# tick-mini-mk-3_0.net
KiCad netlist of a schematic drawn in EAGLE
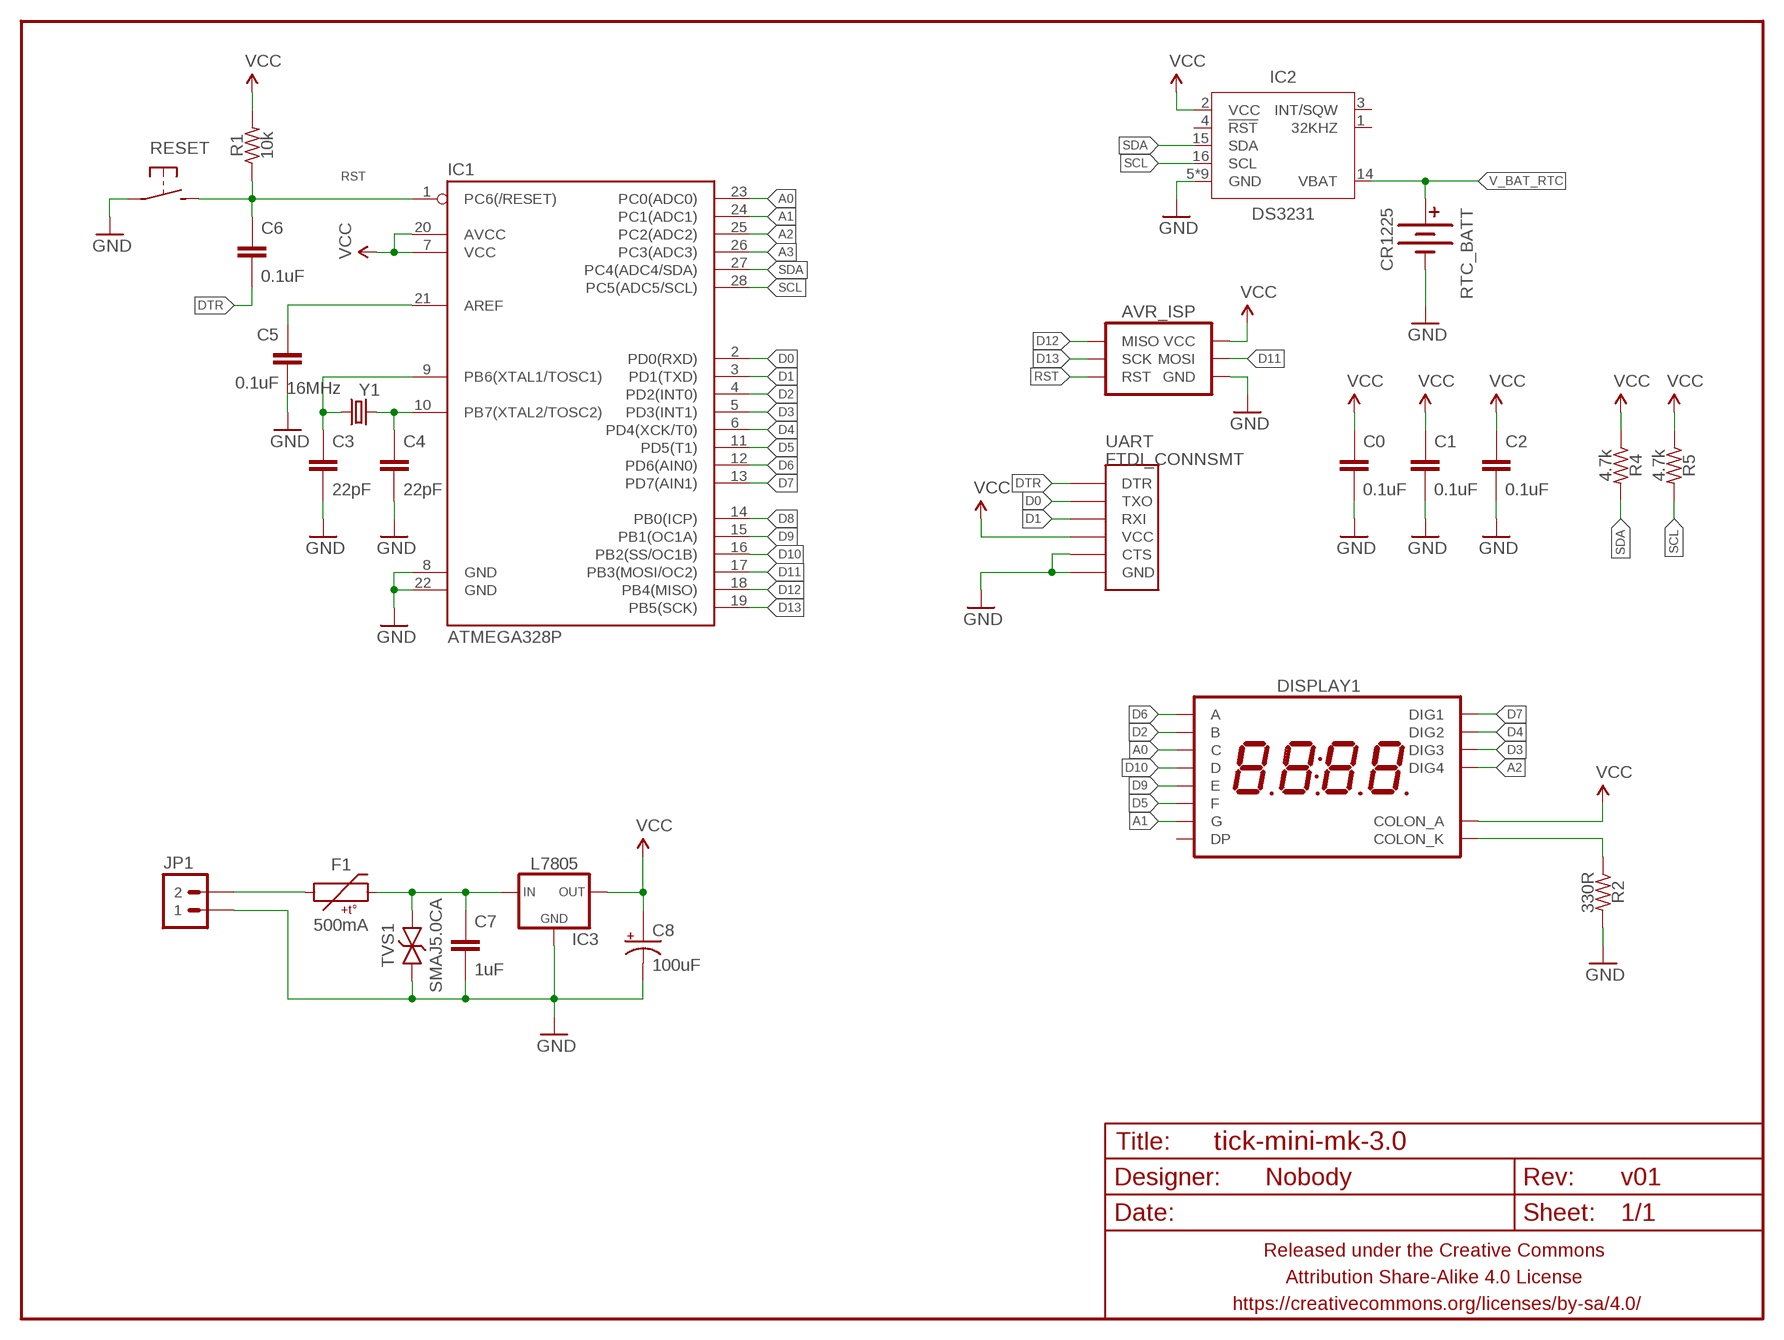
[diagram p0: schematic, sheet 1]

(export (version "E")
  (design (tool "Eeschema 10.0.6"))
  (components
    (comp (ref "AVR_ISP")
      (value "AVR_SPI_PRG_6PTH")
      (footprint "eagle-import:2X3")
      (libsource (lib "eagle-import") (part "AVR_SPI_PRG_6PTH"))
    )
    (comp (ref "C0")
      (value "0.1uF")
      (footprint "eagle-import:C0603")
      (libsource (lib "eagle-import") (part "CAPACITOR-CERAMICC0603"))
    )
    (comp (ref "C1")
      (value "0.1uF")
      (footprint "eagle-import:C0603")
      (libsource (lib "eagle-import") (part "CAPACITOR-CERAMICC0603"))
    )
    (comp (ref "C2")
      (value "0.1uF")
      (footprint "eagle-import:C0603")
      (libsource (lib "eagle-import") (part "CAPACITOR-CERAMICC0603"))
    )
    (comp (ref "C3")
      (value "22pF")
      (footprint "eagle-import:C0603")
      (libsource (lib "eagle-import") (part "CAPACITOR-CERAMICC0603"))
    )
    (comp (ref "C4")
      (value "22pF")
      (footprint "eagle-import:C0603")
      (libsource (lib "eagle-import") (part "CAPACITOR-CERAMICC0603"))
    )
    (comp (ref "C5")
      (value "0.1uF")
      (footprint "eagle-import:C0603")
      (libsource (lib "eagle-import") (part "CAPACITOR-CERAMICC0603"))
    )
    (comp (ref "C6")
      (value "0.1uF")
      (footprint "eagle-import:C0603")
      (libsource (lib "eagle-import") (part "CAPACITOR-CERAMICC0603"))
    )
    (comp (ref "C7")
      (value "1uF")
      (footprint "eagle-import:C0805")
      (libsource (lib "eagle-import") (part "CAPACITOR-CERAMICC0805"))
    )
    (comp (ref "C8")
      (value "100uF")
      (footprint "eagle-import:E2,5-5")
      (libsource (lib "eagle-import") (part "CAPACITOR-POLARIZEDE2.5-5"))
    )
    (comp (ref "DISPLAY1")
      (value "7SEG_4DIGIT_COLON14.2MM-CC-NS")
      (footprint "eagle-import:7SEG_4DIG_NS")
      (libsource (lib "eagle-import") (part "7SEG_4DIGIT_COLON14.2MM-CC-NS"))
    )
    (comp (ref "F1")
      (value "500mA")
      (footprint "eagle-import:PTC-1206")
      (libsource (lib "eagle-import") (part "PTCSMD"))
    )
    (comp (ref "FRAME1")
      (value "FRAME-LETTERNO_PACKAGE")
      (footprint "eagle-import:DUMMY")
      (fields (field (name "DESIGNER") "Nobody"))
      (libsource (lib "eagle-import") (part "FRAME-LETTERNO_PACKAGE"))
    )
    (comp (ref "IC1")
      (value "ATMEGA328P")
      (footprint "eagle-import:DIL28-3")
      (libsource (lib "eagle-import") (part "ATMEGA328P_PDIP"))
    )
    (comp (ref "IC2")
      (value "DS3231")
      (footprint "eagle-import:SO16W")
      (libsource (lib "eagle-import") (part "DS3231"))
    )
    (comp (ref "IC3")
      (value "L7805")
      (footprint "eagle-import:SO08")
      (libsource (lib "eagle-import") (part "V_REG_78XX"))
    )
    (comp (ref "JP1")
      (value "M02PTH-CENTERED-R+")
      (footprint "eagle-import:1X02-CENTER-R+")
      (libsource (lib "eagle-import") (part "M02PTH-CENTERED-R+"))
    )
    (comp (ref "R1")
      (value "10k")
      (footprint "eagle-import:R0603")
      (libsource (lib "eagle-import") (part "RESISTORR0603"))
    )
    (comp (ref "R2")
      (value "330R")
      (footprint "eagle-import:RESISTOR-AXIAL-PTH-7.62MM")
      (libsource (lib "eagle-import") (part "RESISTORPTH-AXIAL-7.62MM"))
    )
    (comp (ref "R4")
      (value "4.7k")
      (footprint "eagle-import:R0603")
      (libsource (lib "eagle-import") (part "RESISTORR0603"))
    )
    (comp (ref "R5")
      (value "4.7k")
      (footprint "eagle-import:R0603")
      (libsource (lib "eagle-import") (part "RESISTORR0603"))
    )
    (comp (ref "RESET")
      (value "SPST-NO-TACT3MM-PTH-SMALL-PADS")
      (footprint "eagle-import:DTS-3-SMALL-PADS")
      (libsource (lib "eagle-import") (part "SPST-NO-TACT3MM-PTH-SMALL-PADS"))
    )
    (comp (ref "RTC_BATT")
      (value "CR1225")
      (footprint "eagle-import:BATTCON_12MM")
      (libsource (lib "eagle-import") (part "BATTERY12MM"))
    )
    (comp (ref "TVS1")
      (value "SMAJ5.0CA")
      (footprint "eagle-import:SMA-DIODE-TVS-BIDIR")
      (libsource (lib "eagle-import") (part "TVSSMA"))
    )
    (comp (ref "UART")
      (value "FTDI_CONNSMT")
      (footprint "eagle-import:FTDI_CONN_SMT")
      (libsource (lib "eagle-import") (part "FTDI_CONNSMT"))
    )
    (comp (ref "Y1")
      (value "16MHz")
      (footprint "eagle-import:HC49U-V")
      (libsource (lib "eagle-import") (part "CRYSTALHC49UV"))
    )
  )
  (nets
    (net (code "1") (name "A0") (class "Default")
      (node (ref "DISPLAY1") (pin "P$4") (pinfunction "C_P$4") (pintype "passive"))
      (node (ref "IC1") (pin "23") (pinfunction "PC0(ADC0)_23") (pintype "bidirectional"))
    )
    (net (code "2") (name "A1") (class "Default")
      (node (ref "DISPLAY1") (pin "P$5") (pinfunction "G_P$5") (pintype "passive"))
      (node (ref "IC1") (pin "24") (pinfunction "PC1(ADC1)_24") (pintype "bidirectional"))
    )
    (net (code "3") (name "A2") (class "Default")
      (node (ref "DISPLAY1") (pin "P$6") (pinfunction "DIG4_P$6") (pintype "passive"))
      (node (ref "IC1") (pin "25") (pinfunction "PC2(ADC2)_25") (pintype "bidirectional"))
    )
    (net (code "4") (name "A3") (class "Default")
      (node (ref "IC1") (pin "26") (pinfunction "PC3(ADC3)_26") (pintype "bidirectional"))
    )
    (net (code "5") (name "D0") (class "Default")
      (node (ref "IC1") (pin "2") (pinfunction "PD0(RXD)_2") (pintype "bidirectional"))
      (node (ref "UART") (pin "TXO") (pinfunction "TXO_TXO") (pintype "bidirectional"))
    )
    (net (code "6") (name "D1") (class "Default")
      (node (ref "IC1") (pin "3") (pinfunction "PD1(TXD)_3") (pintype "bidirectional"))
      (node (ref "UART") (pin "RXI") (pinfunction "RXI_RXI") (pintype "bidirectional"))
    )
    (net (code "7") (name "D2") (class "Default")
      (node (ref "DISPLAY1") (pin "P$9") (pinfunction "B_P$9") (pintype "passive"))
      (node (ref "IC1") (pin "4") (pinfunction "PD2(INT0)_4") (pintype "bidirectional"))
    )
    (net (code "8") (name "D3") (class "Default")
      (node (ref "DISPLAY1") (pin "P$10") (pinfunction "DIG3_P$10") (pintype "passive"))
      (node (ref "IC1") (pin "5") (pinfunction "PD3(INT1)_5") (pintype "bidirectional"))
    )
    (net (code "9") (name "D4") (class "Default")
      (node (ref "DISPLAY1") (pin "P$11") (pinfunction "DIG2_P$11") (pintype "passive"))
      (node (ref "IC1") (pin "6") (pinfunction "PD4(XCK/T0)_6") (pintype "bidirectional"))
    )
    (net (code "10") (name "D5") (class "Default")
      (node (ref "DISPLAY1") (pin "P$12") (pinfunction "F_P$12") (pintype "passive"))
      (node (ref "IC1") (pin "11") (pinfunction "PD5(T1)_11") (pintype "bidirectional"))
    )
    (net (code "11") (name "D6") (class "Default")
      (node (ref "DISPLAY1") (pin "P$13") (pinfunction "A_P$13") (pintype "passive"))
      (node (ref "IC1") (pin "12") (pinfunction "PD6(AIN0)_12") (pintype "bidirectional"))
    )
    (net (code "12") (name "D7") (class "Default")
      (node (ref "DISPLAY1") (pin "P$14") (pinfunction "DIG1_P$14") (pintype "passive"))
      (node (ref "IC1") (pin "13") (pinfunction "PD7(AIN1)_13") (pintype "bidirectional"))
    )
    (net (code "13") (name "D8") (class "Default")
      (node (ref "IC1") (pin "14") (pinfunction "PB0(ICP)_14") (pintype "bidirectional"))
    )
    (net (code "14") (name "D9") (class "Default")
      (node (ref "DISPLAY1") (pin "P$1") (pinfunction "E_P$1") (pintype "passive"))
      (node (ref "IC1") (pin "15") (pinfunction "PB1(OC1A)_15") (pintype "bidirectional"))
    )
    (net (code "15") (name "D10") (class "Default")
      (node (ref "DISPLAY1") (pin "P$2") (pinfunction "D_P$2") (pintype "passive"))
      (node (ref "IC1") (pin "16") (pinfunction "PB2(SS/OC1B)_16") (pintype "bidirectional"))
    )
    (net (code "16") (name "D11") (class "Default")
      (node (ref "AVR_ISP") (pin "4") (pinfunction "MOSI_4") (pintype "passive"))
      (node (ref "IC1") (pin "17") (pinfunction "PB3(MOSI/OC2)_17") (pintype "bidirectional"))
    )
    (net (code "17") (name "D12") (class "Default")
      (node (ref "AVR_ISP") (pin "1") (pinfunction "MISO_1") (pintype "passive"))
      (node (ref "IC1") (pin "18") (pinfunction "PB4(MISO)_18") (pintype "bidirectional"))
    )
    (net (code "18") (name "D13") (class "Default")
      (node (ref "AVR_ISP") (pin "3") (pinfunction "SCK_3") (pintype "passive"))
      (node (ref "IC1") (pin "19") (pinfunction "PB5(SCK)_19") (pintype "bidirectional"))
    )
    (net (code "19") (name "DTR") (class "Default")
      (node (ref "C6") (pin "2") (pinfunction "2_2") (pintype "passive"))
      (node (ref "UART") (pin "DTR") (pinfunction "DTR_DTR") (pintype "bidirectional"))
    )
    (net (code "20") (name "GND") (class "Default")
      (node (ref "AVR_ISP") (pin "6") (pinfunction "GND_6") (pintype "passive"))
      (node (ref "C0") (pin "2") (pinfunction "2_2") (pintype "passive"))
      (node (ref "C1") (pin "2") (pinfunction "2_2") (pintype "passive"))
      (node (ref "C2") (pin "2") (pinfunction "2_2") (pintype "passive"))
      (node (ref "C3") (pin "2") (pinfunction "2_2") (pintype "passive"))
      (node (ref "C4") (pin "2") (pinfunction "2_2") (pintype "passive"))
      (node (ref "C5") (pin "2") (pinfunction "2_2") (pintype "passive"))
      (node (ref "C7") (pin "2") (pinfunction "2_2") (pintype "passive"))
      (node (ref "C8") (pin "-") (pinfunction "-_-") (pintype "passive"))
      (node (ref "IC1") (pin "22") (pinfunction "GND_22") (pintype "bidirectional"))
      (node (ref "IC1") (pin "8") (pinfunction "GND_8") (pintype "bidirectional"))
      (node (ref "IC2") (pin "10") (pinfunction "GND_10") (pintype "bidirectional"))
      (node (ref "IC2") (pin "11") (pinfunction "GND_11") (pintype "bidirectional"))
      (node (ref "IC2") (pin "12") (pinfunction "GND_12") (pintype "bidirectional"))
      (node (ref "IC2") (pin "13") (pinfunction "GND_13") (pintype "bidirectional"))
      (node (ref "IC2") (pin "5") (pinfunction "GND_5") (pintype "bidirectional"))
      (node (ref "IC2") (pin "6") (pinfunction "GND_6") (pintype "bidirectional"))
      (node (ref "IC2") (pin "7") (pinfunction "GND_7") (pintype "bidirectional"))
      (node (ref "IC2") (pin "8") (pinfunction "GND_8") (pintype "bidirectional"))
      (node (ref "IC2") (pin "9") (pinfunction "GND_9") (pintype "bidirectional"))
      (node (ref "IC3") (pin "2") (pinfunction "GND_2") (pintype "bidirectional"))
      (node (ref "IC3") (pin "3") (pinfunction "GND_3") (pintype "bidirectional"))
      (node (ref "IC3") (pin "4") (pinfunction "GND_4") (pintype "bidirectional"))
      (node (ref "IC3") (pin "5") (pinfunction "GND_5") (pintype "bidirectional"))
      (node (ref "IC3") (pin "6") (pinfunction "GND_6") (pintype "bidirectional"))
      (node (ref "IC3") (pin "7") (pinfunction "GND_7") (pintype "bidirectional"))
      (node (ref "JP1") (pin "1") (pinfunction "1_1") (pintype "passive"))
      (node (ref "R2") (pin "P$2") (pinfunction "2_P$2") (pintype "passive"))
      (node (ref "RESET") (pin "1") (pinfunction "1_1") (pintype "passive"))
      (node (ref "RTC_BATT") (pin "GND") (pinfunction "-_GND") (pintype "power_in"))
      (node (ref "TVS1") (pin "1") (pinfunction "1_1") (pintype "passive"))
      (node (ref "UART") (pin "CTS") (pinfunction "CTS_CTS") (pintype "bidirectional"))
      (node (ref "UART") (pin "GND") (pinfunction "GND_GND") (pintype "bidirectional"))
    )
    (net (code "21") (name "Net-(DISPLAY1-COLON_K)") (class "Default")
      (node (ref "DISPLAY1") (pin "P$7") (pinfunction "COLON_K_P$7") (pintype "passive"))
      (node (ref "R2") (pin "P$1") (pinfunction "1_P$1") (pintype "passive"))
    )
    (net (code "22") (name "Net-(F1-Pad1)") (class "Default")
      (node (ref "F1") (pin "1") (pinfunction "1_1") (pintype "passive"))
      (node (ref "JP1") (pin "2") (pinfunction "2_2") (pintype "passive"))
    )
    (net (code "23") (name "Net-(IC1-AREF)") (class "Default")
      (node (ref "C5") (pin "1") (pinfunction "1_1") (pintype "passive"))
      (node (ref "IC1") (pin "21") (pinfunction "AREF_21") (pintype "bidirectional"))
    )
    (net (code "24") (name "Net-(IC1-PB6(XTAL1{slash}TOSC1))") (class "Default")
      (node (ref "C3") (pin "1") (pinfunction "1_1") (pintype "passive"))
      (node (ref "IC1") (pin "9") (pinfunction "PB6(XTAL1/TOSC1)_9") (pintype "bidirectional"))
      (node (ref "Y1") (pin "2") (pinfunction "2_2") (pintype "passive"))
    )
    (net (code "25") (name "Net-(IC1-PB7(XTAL2{slash}TOSC2))") (class "Default")
      (node (ref "C4") (pin "1") (pinfunction "1_1") (pintype "passive"))
      (node (ref "IC1") (pin "10") (pinfunction "PB7(XTAL2/TOSC2)_10") (pintype "bidirectional"))
      (node (ref "Y1") (pin "1") (pinfunction "1_1") (pintype "passive"))
    )
    (net (code "26") (name "Net-(IC3-IN)") (class "Default")
      (node (ref "C7") (pin "1") (pinfunction "1_1") (pintype "passive"))
      (node (ref "F1") (pin "2") (pinfunction "2_2") (pintype "passive"))
      (node (ref "IC3") (pin "8") (pinfunction "IN_8") (pintype "bidirectional"))
      (node (ref "TVS1") (pin "2") (pinfunction "2_2") (pintype "passive"))
    )
    (net (code "27") (name "RST") (class "Default")
      (node (ref "AVR_ISP") (pin "5") (pinfunction "RST_5") (pintype "passive"))
      (node (ref "C6") (pin "1") (pinfunction "1_1") (pintype "passive"))
      (node (ref "IC1") (pin "1") (pinfunction "PC6(/RESET)_1") (pintype "bidirectional"))
      (node (ref "R1") (pin "1") (pinfunction "1_1") (pintype "passive"))
      (node (ref "RESET") (pin "2") (pinfunction "2_2") (pintype "passive"))
    )
    (net (code "28") (name "SCL") (class "Default")
      (node (ref "IC1") (pin "28") (pinfunction "PC5(ADC5/SCL)_28") (pintype "bidirectional"))
      (node (ref "IC2") (pin "16") (pinfunction "SCL_16") (pintype "bidirectional"))
      (node (ref "R5") (pin "2") (pinfunction "2_2") (pintype "passive"))
    )
    (net (code "29") (name "SDA") (class "Default")
      (node (ref "IC1") (pin "27") (pinfunction "PC4(ADC4/SDA)_27") (pintype "bidirectional"))
      (node (ref "IC2") (pin "15") (pinfunction "SDA_15") (pintype "bidirectional"))
      (node (ref "R4") (pin "2") (pinfunction "2_2") (pintype "passive"))
    )
    (net (code "30") (name "VCC") (class "Default")
      (node (ref "AVR_ISP") (pin "2") (pinfunction "VCC_2") (pintype "passive"))
      (node (ref "C0") (pin "1") (pinfunction "1_1") (pintype "passive"))
      (node (ref "C1") (pin "1") (pinfunction "1_1") (pintype "passive"))
      (node (ref "C2") (pin "1") (pinfunction "1_1") (pintype "passive"))
      (node (ref "C8") (pin "+") (pinfunction "+_+") (pintype "passive"))
      (node (ref "DISPLAY1") (pin "P$8") (pinfunction "COLON_A_P$8") (pintype "passive"))
      (node (ref "IC1") (pin "20") (pinfunction "AVCC_20") (pintype "bidirectional"))
      (node (ref "IC1") (pin "7") (pinfunction "VCC_7") (pintype "bidirectional"))
      (node (ref "IC2") (pin "2") (pinfunction "VCC_2") (pintype "bidirectional"))
      (node (ref "IC3") (pin "1") (pinfunction "OUT_1") (pintype "bidirectional"))
      (node (ref "R1") (pin "2") (pinfunction "2_2") (pintype "passive"))
      (node (ref "R4") (pin "1") (pinfunction "1_1") (pintype "passive"))
      (node (ref "R5") (pin "1") (pinfunction "1_1") (pintype "passive"))
      (node (ref "UART") (pin "VCC") (pinfunction "VCC_VCC") (pintype "bidirectional"))
    )
    (net (code "31") (name "V_BAT_RTC") (class "Default")
      (node (ref "IC2") (pin "14") (pinfunction "VBAT_14") (pintype "bidirectional"))
      (node (ref "RTC_BATT") (pin "PWR@1") (pinfunction "+_PWR@1") (pintype "power_in"))
    )
    (net (code "32") (name "unconnected-(DISPLAY1-DP-PadP$3)") (class "Default")
      (node (ref "DISPLAY1") (pin "P$3") (pinfunction "DP_P$3") (pintype "passive"))
    )
    (net (code "33") (name "unconnected-(IC2-32KHZ-Pad1)") (class "Default")
      (node (ref "IC2") (pin "1") (pinfunction "32KHZ_1") (pintype "bidirectional"))
    )
    (net (code "34") (name "unconnected-(IC2-INT{slash}SQW-Pad3)") (class "Default")
      (node (ref "IC2") (pin "3") (pinfunction "INT/SQW_3") (pintype "bidirectional"))
    )
    (net (code "35") (name "unconnected-(IC2-~{RST}-Pad4)") (class "Default")
      (node (ref "IC2") (pin "4") (pinfunction "~{RST}_4") (pintype "bidirectional"))
    )
  )
)
